# Schematics1.net
KiCad netlist of a schematic drawn in EAGLE
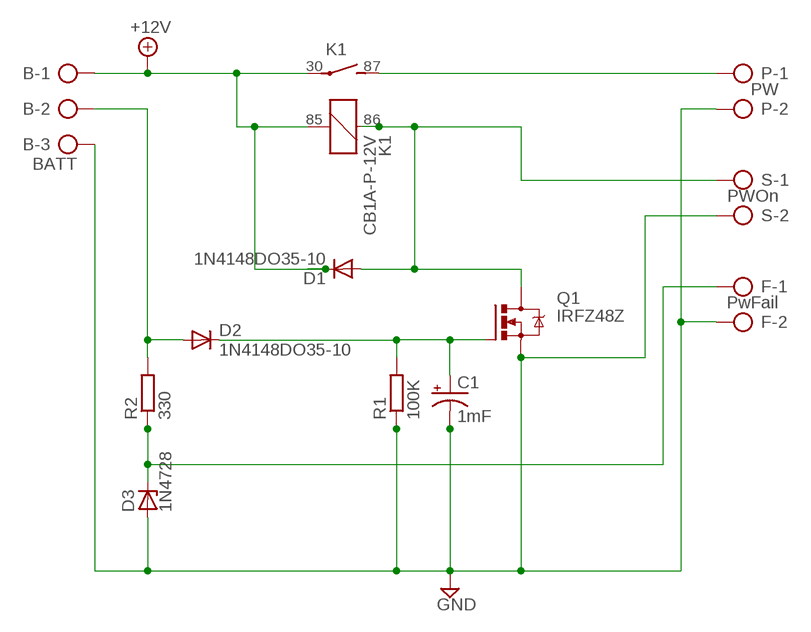
[diagram p0: schematic, sheet 1]

(export (version "E")
  (design (tool "Eeschema 10.0.6"))
  (components
    (comp (ref "B")
      (value "BATT")
      (footprint "eagle-import:AK300_3")
      (libsource (lib "eagle-import") (part "AK300/3"))
    )
    (comp (ref "C1")
      (value "1mF")
      (footprint "eagle-import:EB20D")
      (libsource (lib "eagle-import") (part "CPOL-USE10-20"))
    )
    (comp (ref "D1")
      (value "1N4148DO35-10")
      (footprint "eagle-import:DO35-10")
      (libsource (lib "eagle-import") (part "1N4148DO35-10"))
    )
    (comp (ref "D2")
      (value "1N4148DO35-10")
      (footprint "eagle-import:DO35-10")
      (libsource (lib "eagle-import") (part "1N4148DO35-10"))
    )
    (comp (ref "D3")
      (value "1N4728")
      (footprint "eagle-import:DO41Z10")
      (libsource (lib "eagle-import") (part "1N4728"))
    )
    (comp (ref "F")
      (value "PwFail")
      (footprint "eagle-import:AK300_2")
      (libsource (lib "eagle-import") (part "AK300/2"))
    )
    (comp (ref "K1")
      (value "CB1A-P-12V")
      (footprint "eagle-import:CB1")
      (fields (field (name "MF") "AROMAT/ MATSUSHITA"))
      (libsource (lib "eagle-import") (part "CB1A-P-12V"))
    )
    (comp (ref "P")
      (value "PW")
      (footprint "eagle-import:AK300_2")
      (libsource (lib "eagle-import") (part "AK300/2"))
    )
    (comp (ref "Q1")
      (value "IRFZ48Z")
      (footprint "eagle-import:TO220BH")
      (libsource (lib "eagle-import") (part "IRFZ48Z"))
    )
    (comp (ref "R1")
      (value "100K")
      (footprint "eagle-import:0207_12")
      (libsource (lib "eagle-import") (part "R-EU_0207/12"))
    )
    (comp (ref "R2")
      (value "330")
      (footprint "eagle-import:0207_12")
      (libsource (lib "eagle-import") (part "R-EU_0207/12"))
    )
    (comp (ref "S")
      (value "PWOn")
      (footprint "eagle-import:AK300_2")
      (libsource (lib "eagle-import") (part "AK300/2"))
    )
  )
  (nets
    (net (code "1") (name "+12V") (class "Default")
      (node (ref "B") (pin "1") (pinfunction "KL_1") (pintype "passive"))
      (node (ref "D1") (pin "C") (pinfunction "C_C") (pintype "passive"))
      (node (ref "K1") (pin "30") (pinfunction "P_30") (pintype "passive"))
      (node (ref "K1") (pin "85") (pinfunction "2_85") (pintype "passive"))
    )
    (net (code "2") (name "GND") (class "Default")
      (node (ref "B") (pin "3") (pinfunction "KL_3") (pintype "passive"))
      (node (ref "C1") (pin "-") (pinfunction "-_-") (pintype "passive"))
      (node (ref "D3") (pin "A") (pinfunction "A_A") (pintype "passive"))
      (node (ref "F") (pin "2") (pinfunction "KL_2") (pintype "passive"))
      (node (ref "P") (pin "2") (pinfunction "KL_2") (pintype "passive"))
      (node (ref "Q1") (pin "S") (pinfunction "S_S") (pintype "passive"))
      (node (ref "R1") (pin "1") (pinfunction "1_1") (pintype "passive"))
      (node (ref "S") (pin "2") (pinfunction "KL_2") (pintype "passive"))
    )
    (net (code "3") (name "Net-(BB-KL)") (class "Default")
      (node (ref "B") (pin "2") (pinfunction "KL_2") (pintype "passive"))
      (node (ref "D2") (pin "A") (pinfunction "A_A") (pintype "passive"))
      (node (ref "R2") (pin "2") (pinfunction "2_2") (pintype "passive"))
    )
    (net (code "4") (name "Net-(C1-Pad+)") (class "Default")
      (node (ref "C1") (pin "+") (pinfunction "+_+") (pintype "passive"))
      (node (ref "D2") (pin "C") (pinfunction "C_C") (pintype "passive"))
      (node (ref "Q1") (pin "G") (pinfunction "G_G") (pintype "passive"))
      (node (ref "R1") (pin "2") (pinfunction "2_2") (pintype "passive"))
    )
    (net (code "5") (name "Net-(FA-KL)") (class "Default")
      (node (ref "D3") (pin "C") (pinfunction "C_C") (pintype "passive"))
      (node (ref "F") (pin "1") (pinfunction "KL_1") (pintype "passive"))
      (node (ref "R2") (pin "1") (pinfunction "1_1") (pintype "passive"))
    )
    (net (code "6") (name "Net-(K1A-1)") (class "Default")
      (node (ref "D1") (pin "A") (pinfunction "A_A") (pintype "passive"))
      (node (ref "K1") (pin "86") (pinfunction "1_86") (pintype "passive"))
      (node (ref "Q1") (pin "D") (pinfunction "D_D") (pintype "passive"))
      (node (ref "S") (pin "1") (pinfunction "KL_1") (pintype "passive"))
    )
    (net (code "7") (name "Net-(K1B-S)") (class "Default")
      (node (ref "K1") (pin "87") (pinfunction "S_87") (pintype "passive"))
      (node (ref "P") (pin "1") (pinfunction "KL_1") (pintype "passive"))
    )
  )
)
